# addonv2.net
KiCad netlist of a schematic drawn in EAGLE
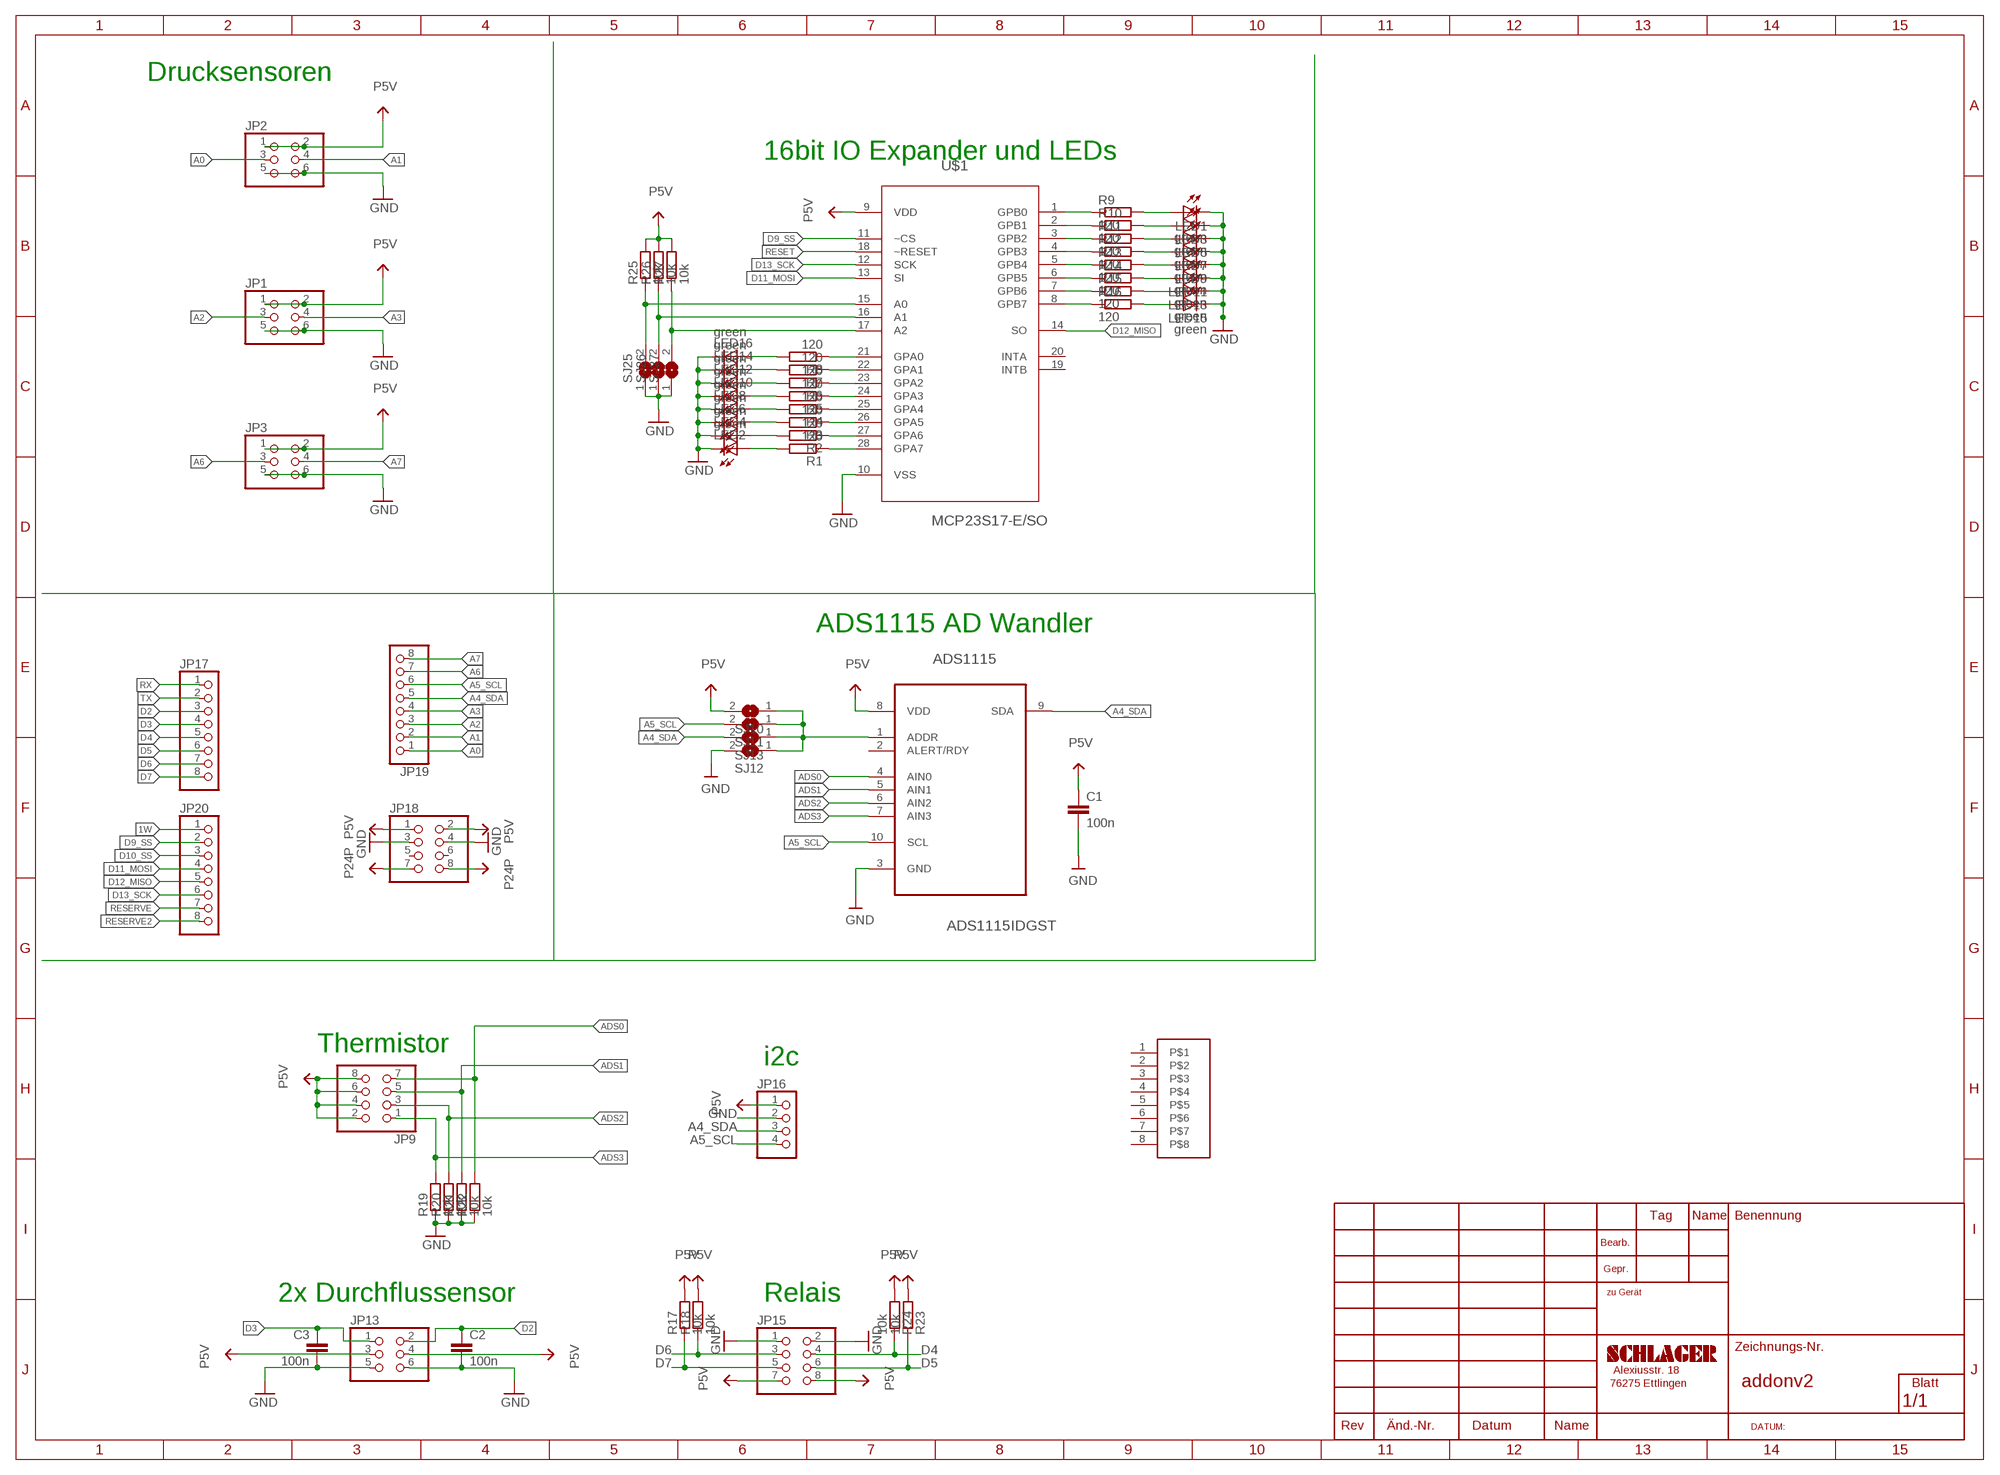
[diagram p0: schematic, sheet 1]

(export (version "E")
  (design (tool "Eeschema 10.0.6"))
  (components
    (comp (ref "ADS1115")
      (value "ADS1115IDGST")
      (footprint "eagle-import:SOP50P490X110-10N")
      (libsource (lib "eagle-import") (part "ADS1115IDGST"))
    )
    (comp (ref "C1")
      (value "100n")
      (footprint "eagle-import:C0805")
      (libsource (lib "eagle-import") (part "C-EUC0805"))
    )
    (comp (ref "C2")
      (value "100n")
      (footprint "eagle-import:C0805")
      (libsource (lib "eagle-import") (part "C-EUC0805"))
    )
    (comp (ref "C3")
      (value "100n")
      (footprint "eagle-import:C0805")
      (libsource (lib "eagle-import") (part "C-EUC0805"))
    )
    (comp (ref "JP1")
      (value "PINHD-2X3/90")
      (footprint "eagle-import:2X03_90")
      (libsource (lib "eagle-import") (part "PINHD-2X3/90"))
    )
    (comp (ref "JP2")
      (value "PINHD-2X3/90")
      (footprint "eagle-import:2X03_90")
      (libsource (lib "eagle-import") (part "PINHD-2X3/90"))
    )
    (comp (ref "JP3")
      (value "PINHD-2X3/90")
      (footprint "eagle-import:2X03_90")
      (libsource (lib "eagle-import") (part "PINHD-2X3/90"))
    )
    (comp (ref "JP9")
      (value "PINHD-2X4/90")
      (footprint "eagle-import:2X04_90")
      (libsource (lib "eagle-import") (part "PINHD-2X4/90"))
    )
    (comp (ref "JP13")
      (value "PINHD-2X3/90")
      (footprint "eagle-import:2X03_90")
      (libsource (lib "eagle-import") (part "PINHD-2X3/90"))
    )
    (comp (ref "JP15")
      (value "PINHD-2X4/90")
      (footprint "eagle-import:2X04_90")
      (libsource (lib "eagle-import") (part "PINHD-2X4/90"))
    )
    (comp (ref "JP16")
      (value "PINHD-1X4/90")
      (footprint "eagle-import:1X04_90")
      (libsource (lib "eagle-import") (part "PINHD-1X4/90"))
    )
    (comp (ref "JP17")
      (value "PINHD-1X8")
      (footprint "eagle-import:1X08")
      (libsource (lib "eagle-import") (part "PINHD-1X8"))
    )
    (comp (ref "JP18")
      (value "PINHD-2X4")
      (footprint "eagle-import:2X04")
      (libsource (lib "eagle-import") (part "PINHD-2X4"))
    )
    (comp (ref "JP19")
      (value "PINHD-1X8")
      (footprint "eagle-import:1X08")
      (libsource (lib "eagle-import") (part "PINHD-1X8"))
    )
    (comp (ref "JP20")
      (value "PINHD-1X8")
      (footprint "eagle-import:1X08")
      (libsource (lib "eagle-import") (part "PINHD-1X8"))
    )
    (comp (ref "LED1")
      (value "green")
      (footprint "eagle-import:CHIPLED_0805")
      (libsource (lib "eagle-import") (part "LEDCHIPLED_0805"))
    )
    (comp (ref "LED2")
      (value "green")
      (footprint "eagle-import:CHIPLED_0805")
      (libsource (lib "eagle-import") (part "LEDCHIPLED_0805"))
    )
    (comp (ref "LED3")
      (value "green")
      (footprint "eagle-import:CHIPLED_0805")
      (libsource (lib "eagle-import") (part "LEDCHIPLED_0805"))
    )
    (comp (ref "LED4")
      (value "green")
      (footprint "eagle-import:CHIPLED_0805")
      (libsource (lib "eagle-import") (part "LEDCHIPLED_0805"))
    )
    (comp (ref "LED5")
      (value "green")
      (footprint "eagle-import:CHIPLED_0805")
      (libsource (lib "eagle-import") (part "LEDCHIPLED_0805"))
    )
    (comp (ref "LED6")
      (value "green")
      (footprint "eagle-import:CHIPLED_0805")
      (libsource (lib "eagle-import") (part "LEDCHIPLED_0805"))
    )
    (comp (ref "LED7")
      (value "green")
      (footprint "eagle-import:CHIPLED_0805")
      (libsource (lib "eagle-import") (part "LEDCHIPLED_0805"))
    )
    (comp (ref "LED8")
      (value "green")
      (footprint "eagle-import:CHIPLED_0805")
      (libsource (lib "eagle-import") (part "LEDCHIPLED_0805"))
    )
    (comp (ref "LED9")
      (value "green")
      (footprint "eagle-import:CHIPLED_0805")
      (libsource (lib "eagle-import") (part "LEDCHIPLED_0805"))
    )
    (comp (ref "LED10")
      (value "green")
      (footprint "eagle-import:CHIPLED_0805")
      (libsource (lib "eagle-import") (part "LEDCHIPLED_0805"))
    )
    (comp (ref "LED11")
      (value "green")
      (footprint "eagle-import:CHIPLED_0805")
      (libsource (lib "eagle-import") (part "LEDCHIPLED_0805"))
    )
    (comp (ref "LED12")
      (value "green")
      (footprint "eagle-import:CHIPLED_0805")
      (libsource (lib "eagle-import") (part "LEDCHIPLED_0805"))
    )
    (comp (ref "LED13")
      (value "green")
      (footprint "eagle-import:CHIPLED_0805")
      (libsource (lib "eagle-import") (part "LEDCHIPLED_0805"))
    )
    (comp (ref "LED14")
      (value "green")
      (footprint "eagle-import:CHIPLED_0805")
      (libsource (lib "eagle-import") (part "LEDCHIPLED_0805"))
    )
    (comp (ref "LED15")
      (value "green")
      (footprint "eagle-import:CHIPLED_0805")
      (libsource (lib "eagle-import") (part "LEDCHIPLED_0805"))
    )
    (comp (ref "LED16")
      (value "green")
      (footprint "eagle-import:CHIPLED_0805")
      (libsource (lib "eagle-import") (part "LEDCHIPLED_0805"))
    )
    (comp (ref "R1")
      (value "120")
      (footprint "eagle-import:R0805")
      (libsource (lib "eagle-import") (part "R-EU_R0805"))
    )
    (comp (ref "R2")
      (value "120")
      (footprint "eagle-import:R0805")
      (libsource (lib "eagle-import") (part "R-EU_R0805"))
    )
    (comp (ref "R3")
      (value "120")
      (footprint "eagle-import:R0805")
      (libsource (lib "eagle-import") (part "R-EU_R0805"))
    )
    (comp (ref "R4")
      (value "120")
      (footprint "eagle-import:R0805")
      (libsource (lib "eagle-import") (part "R-EU_R0805"))
    )
    (comp (ref "R5")
      (value "120")
      (footprint "eagle-import:R0805")
      (libsource (lib "eagle-import") (part "R-EU_R0805"))
    )
    (comp (ref "R6")
      (value "120")
      (footprint "eagle-import:R0805")
      (libsource (lib "eagle-import") (part "R-EU_R0805"))
    )
    (comp (ref "R7")
      (value "120")
      (footprint "eagle-import:R0805")
      (libsource (lib "eagle-import") (part "R-EU_R0805"))
    )
    (comp (ref "R8")
      (value "120")
      (footprint "eagle-import:R0805")
      (libsource (lib "eagle-import") (part "R-EU_R0805"))
    )
    (comp (ref "R9")
      (value "120")
      (footprint "eagle-import:R0805")
      (libsource (lib "eagle-import") (part "R-EU_R0805"))
    )
    (comp (ref "R10")
      (value "120")
      (footprint "eagle-import:R0805")
      (libsource (lib "eagle-import") (part "R-EU_R0805"))
    )
    (comp (ref "R11")
      (value "120")
      (footprint "eagle-import:R0805")
      (libsource (lib "eagle-import") (part "R-EU_R0805"))
    )
    (comp (ref "R12")
      (value "120")
      (footprint "eagle-import:R0805")
      (libsource (lib "eagle-import") (part "R-EU_R0805"))
    )
    (comp (ref "R13")
      (value "120")
      (footprint "eagle-import:R0805")
      (libsource (lib "eagle-import") (part "R-EU_R0805"))
    )
    (comp (ref "R14")
      (value "120")
      (footprint "eagle-import:R0805")
      (libsource (lib "eagle-import") (part "R-EU_R0805"))
    )
    (comp (ref "R15")
      (value "120")
      (footprint "eagle-import:R0805")
      (libsource (lib "eagle-import") (part "R-EU_R0805"))
    )
    (comp (ref "R16")
      (value "120")
      (footprint "eagle-import:R0805")
      (libsource (lib "eagle-import") (part "R-EU_R0805"))
    )
    (comp (ref "R17")
      (value "10k")
      (footprint "eagle-import:R0805")
      (libsource (lib "eagle-import") (part "R-EU_R0805"))
    )
    (comp (ref "R18")
      (value "10k")
      (footprint "eagle-import:R0805")
      (libsource (lib "eagle-import") (part "R-EU_R0805"))
    )
    (comp (ref "R19")
      (value "10k")
      (footprint "eagle-import:R0805")
      (libsource (lib "eagle-import") (part "R-EU_R0805"))
    )
    (comp (ref "R20")
      (value "10k")
      (footprint "eagle-import:R0805")
      (libsource (lib "eagle-import") (part "R-EU_R0805"))
    )
    (comp (ref "R21")
      (value "10k")
      (footprint "eagle-import:R0805")
      (libsource (lib "eagle-import") (part "R-EU_R0805"))
    )
    (comp (ref "R22")
      (value "10k")
      (footprint "eagle-import:R0805")
      (libsource (lib "eagle-import") (part "R-EU_R0805"))
    )
    (comp (ref "R23")
      (value "10k")
      (footprint "eagle-import:R0805")
      (libsource (lib "eagle-import") (part "R-EU_R0805"))
    )
    (comp (ref "R24")
      (value "10k")
      (footprint "eagle-import:R0805")
      (libsource (lib "eagle-import") (part "R-EU_R0805"))
    )
    (comp (ref "R25")
      (value "10k")
      (footprint "eagle-import:R0805")
      (libsource (lib "eagle-import") (part "R-EU_R0805"))
    )
    (comp (ref "R26")
      (value "10k")
      (footprint "eagle-import:R0805")
      (libsource (lib "eagle-import") (part "R-EU_R0805"))
    )
    (comp (ref "R27")
      (value "10k")
      (footprint "eagle-import:R0805")
      (libsource (lib "eagle-import") (part "R-EU_R0805"))
    )
    (comp (ref "SJ10")
      (value "SJN")
      (footprint "eagle-import:SJ")
      (libsource (lib "eagle-import") (part "SJN"))
    )
    (comp (ref "SJ11")
      (value "SJN")
      (footprint "eagle-import:SJ")
      (libsource (lib "eagle-import") (part "SJN"))
    )
    (comp (ref "SJ12")
      (value "SJN")
      (footprint "eagle-import:SJ")
      (libsource (lib "eagle-import") (part "SJN"))
    )
    (comp (ref "SJ13")
      (value "SJN")
      (footprint "eagle-import:SJ")
      (libsource (lib "eagle-import") (part "SJN"))
    )
    (comp (ref "SJ25")
      (value "SJN")
      (footprint "eagle-import:SJ")
      (libsource (lib "eagle-import") (part "SJN"))
    )
    (comp (ref "SJ26")
      (value "SJN")
      (footprint "eagle-import:SJ")
      (libsource (lib "eagle-import") (part "SJN"))
    )
    (comp (ref "SJ27")
      (value "SJN")
      (footprint "eagle-import:SJ")
      (libsource (lib "eagle-import") (part "SJN"))
    )
    (comp (ref "U$1")
      (value "MCP23S17-E/SO")
      (footprint "eagle-import:SOIC127P030X265-28N")
      (libsource (lib "eagle-import") (part "MCP23S17-E/SO"))
    )
    (comp (ref "U$2")
      (value "1.44-128X128")
      (footprint "eagle-import:1.44-128X128")
      (libsource (lib "eagle-import") (part "1.44-128X128"))
    )
  )
  (nets
    (net (code "1") (name "1W") (class "Default")
      (node (ref "JP20") (pin "1") (pinfunction "1_1") (pintype "passive"))
    )
    (net (code "2") (name "A0") (class "Default")
      (node (ref "JP19") (pin "1") (pinfunction "1_1") (pintype "passive"))
      (node (ref "JP2") (pin "3") (pinfunction "3_3") (pintype "passive"))
    )
    (net (code "3") (name "A1") (class "Default")
      (node (ref "JP19") (pin "2") (pinfunction "2_2") (pintype "passive"))
      (node (ref "JP2") (pin "4") (pinfunction "4_4") (pintype "passive"))
    )
    (net (code "4") (name "A2") (class "Default")
      (node (ref "JP1") (pin "3") (pinfunction "3_3") (pintype "passive"))
      (node (ref "JP19") (pin "3") (pinfunction "3_3") (pintype "passive"))
    )
    (net (code "5") (name "A3") (class "Default")
      (node (ref "JP1") (pin "4") (pinfunction "4_4") (pintype "passive"))
      (node (ref "JP19") (pin "4") (pinfunction "4_4") (pintype "passive"))
    )
    (net (code "6") (name "A4_SDA") (class "Default")
      (node (ref "ADS1115") (pin "9") (pinfunction "SDA_9") (pintype "bidirectional"))
      (node (ref "JP16") (pin "3") (pinfunction "3_3") (pintype "passive"))
      (node (ref "JP19") (pin "5") (pinfunction "5_5") (pintype "passive"))
      (node (ref "SJ13") (pin "2") (pinfunction "2_2") (pintype "passive"))
    )
    (net (code "7") (name "A5_SCL") (class "Default")
      (node (ref "ADS1115") (pin "10") (pinfunction "SCL_10") (pintype "input"))
      (node (ref "JP16") (pin "4") (pinfunction "4_4") (pintype "passive"))
      (node (ref "JP19") (pin "6") (pinfunction "6_6") (pintype "passive"))
      (node (ref "SJ11") (pin "2") (pinfunction "2_2") (pintype "passive"))
    )
    (net (code "8") (name "A6") (class "Default")
      (node (ref "JP19") (pin "7") (pinfunction "7_7") (pintype "passive"))
      (node (ref "JP3") (pin "3") (pinfunction "3_3") (pintype "passive"))
    )
    (net (code "9") (name "A7") (class "Default")
      (node (ref "JP19") (pin "8") (pinfunction "8_8") (pintype "passive"))
      (node (ref "JP3") (pin "4") (pinfunction "4_4") (pintype "passive"))
    )
    (net (code "10") (name "ADS0") (class "Default")
      (node (ref "ADS1115") (pin "4") (pinfunction "AIN0_4") (pintype "input"))
      (node (ref "JP9") (pin "7") (pinfunction "7_7") (pintype "passive"))
      (node (ref "R22") (pin "2") (pinfunction "2_2") (pintype "passive"))
    )
    (net (code "11") (name "ADS1") (class "Default")
      (node (ref "ADS1115") (pin "5") (pinfunction "AIN1_5") (pintype "input"))
      (node (ref "JP9") (pin "5") (pinfunction "5_5") (pintype "passive"))
      (node (ref "R21") (pin "2") (pinfunction "2_2") (pintype "passive"))
    )
    (net (code "12") (name "ADS2") (class "Default")
      (node (ref "ADS1115") (pin "6") (pinfunction "AIN2_6") (pintype "input"))
      (node (ref "JP9") (pin "3") (pinfunction "3_3") (pintype "passive"))
      (node (ref "R20") (pin "2") (pinfunction "2_2") (pintype "passive"))
    )
    (net (code "13") (name "ADS3") (class "Default")
      (node (ref "ADS1115") (pin "7") (pinfunction "AIN3_7") (pintype "input"))
      (node (ref "JP9") (pin "1") (pinfunction "1_1") (pintype "passive"))
      (node (ref "R19") (pin "2") (pinfunction "2_2") (pintype "passive"))
    )
    (net (code "14") (name "D2") (class "Default")
      (node (ref "C2") (pin "1") (pinfunction "1_1") (pintype "passive"))
      (node (ref "JP13") (pin "2") (pinfunction "2_2") (pintype "passive"))
      (node (ref "JP17") (pin "3") (pinfunction "3_3") (pintype "passive"))
    )
    (net (code "15") (name "D3") (class "Default")
      (node (ref "C3") (pin "1") (pinfunction "1_1") (pintype "passive"))
      (node (ref "JP13") (pin "1") (pinfunction "1_1") (pintype "passive"))
      (node (ref "JP17") (pin "4") (pinfunction "4_4") (pintype "passive"))
    )
    (net (code "16") (name "D4") (class "Default")
      (node (ref "JP15") (pin "4") (pinfunction "4_4") (pintype "passive"))
      (node (ref "JP17") (pin "5") (pinfunction "5_5") (pintype "passive"))
      (node (ref "R24") (pin "1") (pinfunction "1_1") (pintype "passive"))
    )
    (net (code "17") (name "D5") (class "Default")
      (node (ref "JP15") (pin "6") (pinfunction "6_6") (pintype "passive"))
      (node (ref "JP17") (pin "6") (pinfunction "6_6") (pintype "passive"))
      (node (ref "R23") (pin "1") (pinfunction "1_1") (pintype "passive"))
    )
    (net (code "18") (name "D6") (class "Default")
      (node (ref "JP15") (pin "3") (pinfunction "3_3") (pintype "passive"))
      (node (ref "JP17") (pin "7") (pinfunction "7_7") (pintype "passive"))
      (node (ref "R18") (pin "1") (pinfunction "1_1") (pintype "passive"))
    )
    (net (code "19") (name "D7") (class "Default")
      (node (ref "JP15") (pin "5") (pinfunction "5_5") (pintype "passive"))
      (node (ref "JP17") (pin "8") (pinfunction "8_8") (pintype "passive"))
      (node (ref "R17") (pin "1") (pinfunction "1_1") (pintype "passive"))
    )
    (net (code "20") (name "D9_SS") (class "Default")
      (node (ref "JP20") (pin "2") (pinfunction "2_2") (pintype "passive"))
      (node (ref "U$1") (pin "11") (pinfunction "~{CS}_11") (pintype "input"))
    )
    (net (code "21") (name "D10_SS") (class "Default")
      (node (ref "JP20") (pin "3") (pinfunction "3_3") (pintype "passive"))
    )
    (net (code "22") (name "D11_MOSI") (class "Default")
      (node (ref "JP20") (pin "4") (pinfunction "4_4") (pintype "passive"))
      (node (ref "U$1") (pin "13") (pinfunction "SI_13") (pintype "input"))
    )
    (net (code "23") (name "D12_MISO") (class "Default")
      (node (ref "JP20") (pin "5") (pinfunction "5_5") (pintype "passive"))
      (node (ref "U$1") (pin "14") (pinfunction "SO_14") (pintype "output"))
    )
    (net (code "24") (name "D13_SCK") (class "Default")
      (node (ref "JP20") (pin "6") (pinfunction "6_6") (pintype "passive"))
      (node (ref "U$1") (pin "12") (pinfunction "SCK_12") (pintype "input"))
    )
    (net (code "25") (name "GND") (class "Default")
      (node (ref "ADS1115") (pin "3") (pinfunction "GND_3") (pintype "passive"))
      (node (ref "C1") (pin "2") (pinfunction "2_2") (pintype "passive"))
      (node (ref "C2") (pin "2") (pinfunction "2_2") (pintype "passive"))
      (node (ref "C3") (pin "2") (pinfunction "2_2") (pintype "passive"))
      (node (ref "JP1") (pin "5") (pinfunction "5_5") (pintype "passive"))
      (node (ref "JP1") (pin "6") (pinfunction "6_6") (pintype "passive"))
      (node (ref "JP13") (pin "5") (pinfunction "5_5") (pintype "passive"))
      (node (ref "JP13") (pin "6") (pinfunction "6_6") (pintype "passive"))
      (node (ref "JP15") (pin "1") (pinfunction "1_1") (pintype "passive"))
      (node (ref "JP15") (pin "2") (pinfunction "2_2") (pintype "passive"))
      (node (ref "JP16") (pin "2") (pinfunction "2_2") (pintype "passive"))
      (node (ref "JP18") (pin "3") (pinfunction "3_3") (pintype "passive"))
      (node (ref "JP18") (pin "4") (pinfunction "4_4") (pintype "passive"))
      (node (ref "JP2") (pin "5") (pinfunction "5_5") (pintype "passive"))
      (node (ref "JP2") (pin "6") (pinfunction "6_6") (pintype "passive"))
      (node (ref "JP3") (pin "5") (pinfunction "5_5") (pintype "passive"))
      (node (ref "JP3") (pin "6") (pinfunction "6_6") (pintype "passive"))
      (node (ref "LED1") (pin "C") (pinfunction "C_C") (pintype "passive"))
      (node (ref "LED10") (pin "C") (pinfunction "C_C") (pintype "passive"))
      (node (ref "LED11") (pin "C") (pinfunction "C_C") (pintype "passive"))
      (node (ref "LED12") (pin "C") (pinfunction "C_C") (pintype "passive"))
      (node (ref "LED13") (pin "C") (pinfunction "C_C") (pintype "passive"))
      (node (ref "LED14") (pin "C") (pinfunction "C_C") (pintype "passive"))
      (node (ref "LED15") (pin "C") (pinfunction "C_C") (pintype "passive"))
      (node (ref "LED16") (pin "C") (pinfunction "C_C") (pintype "passive"))
      (node (ref "LED2") (pin "C") (pinfunction "C_C") (pintype "passive"))
      (node (ref "LED3") (pin "C") (pinfunction "C_C") (pintype "passive"))
      (node (ref "LED4") (pin "C") (pinfunction "C_C") (pintype "passive"))
      (node (ref "LED5") (pin "C") (pinfunction "C_C") (pintype "passive"))
      (node (ref "LED6") (pin "C") (pinfunction "C_C") (pintype "passive"))
      (node (ref "LED7") (pin "C") (pinfunction "C_C") (pintype "passive"))
      (node (ref "LED8") (pin "C") (pinfunction "C_C") (pintype "passive"))
      (node (ref "LED9") (pin "C") (pinfunction "C_C") (pintype "passive"))
      (node (ref "R19") (pin "1") (pinfunction "1_1") (pintype "passive"))
      (node (ref "R20") (pin "1") (pinfunction "1_1") (pintype "passive"))
      (node (ref "R21") (pin "1") (pinfunction "1_1") (pintype "passive"))
      (node (ref "R22") (pin "1") (pinfunction "1_1") (pintype "passive"))
      (node (ref "SJ12") (pin "2") (pinfunction "2_2") (pintype "passive"))
      (node (ref "SJ25") (pin "1") (pinfunction "1_1") (pintype "passive"))
      (node (ref "SJ26") (pin "1") (pinfunction "1_1") (pintype "passive"))
      (node (ref "SJ27") (pin "1") (pinfunction "1_1") (pintype "passive"))
      (node (ref "U$1") (pin "10") (pinfunction "VSS_10") (pintype "power_in"))
    )
    (net (code "26") (name "Net-(ADS1115-ADDR)") (class "Default")
      (node (ref "ADS1115") (pin "1") (pinfunction "ADDR_1") (pintype "input"))
      (node (ref "SJ10") (pin "1") (pinfunction "1_1") (pintype "passive"))
      (node (ref "SJ11") (pin "1") (pinfunction "1_1") (pintype "passive"))
      (node (ref "SJ12") (pin "1") (pinfunction "1_1") (pintype "passive"))
      (node (ref "SJ13") (pin "1") (pinfunction "1_1") (pintype "passive"))
    )
    (net (code "27") (name "Net-(LED1-PadA)") (class "Default")
      (node (ref "LED1") (pin "A") (pinfunction "A_A") (pintype "passive"))
      (node (ref "R9") (pin "2") (pinfunction "2_2") (pintype "passive"))
    )
    (net (code "28") (name "Net-(LED2-PadA)") (class "Default")
      (node (ref "LED2") (pin "A") (pinfunction "A_A") (pintype "passive"))
      (node (ref "R1") (pin "2") (pinfunction "2_2") (pintype "passive"))
    )
    (net (code "29") (name "Net-(LED3-PadA)") (class "Default")
      (node (ref "LED3") (pin "A") (pinfunction "A_A") (pintype "passive"))
      (node (ref "R10") (pin "2") (pinfunction "2_2") (pintype "passive"))
    )
    (net (code "30") (name "Net-(LED4-PadA)") (class "Default")
      (node (ref "LED4") (pin "A") (pinfunction "A_A") (pintype "passive"))
      (node (ref "R2") (pin "2") (pinfunction "2_2") (pintype "passive"))
    )
    (net (code "31") (name "Net-(LED5-PadA)") (class "Default")
      (node (ref "LED5") (pin "A") (pinfunction "A_A") (pintype "passive"))
      (node (ref "R11") (pin "2") (pinfunction "2_2") (pintype "passive"))
    )
    (net (code "32") (name "Net-(LED6-PadA)") (class "Default")
      (node (ref "LED6") (pin "A") (pinfunction "A_A") (pintype "passive"))
      (node (ref "R3") (pin "2") (pinfunction "2_2") (pintype "passive"))
    )
    (net (code "33") (name "Net-(LED7-PadA)") (class "Default")
      (node (ref "LED7") (pin "A") (pinfunction "A_A") (pintype "passive"))
      (node (ref "R12") (pin "2") (pinfunction "2_2") (pintype "passive"))
    )
    (net (code "34") (name "Net-(LED8-PadA)") (class "Default")
      (node (ref "LED8") (pin "A") (pinfunction "A_A") (pintype "passive"))
      (node (ref "R4") (pin "2") (pinfunction "2_2") (pintype "passive"))
    )
    (net (code "35") (name "Net-(LED9-PadA)") (class "Default")
      (node (ref "LED9") (pin "A") (pinfunction "A_A") (pintype "passive"))
      (node (ref "R13") (pin "2") (pinfunction "2_2") (pintype "passive"))
    )
    (net (code "36") (name "Net-(LED10-PadA)") (class "Default")
      (node (ref "LED10") (pin "A") (pinfunction "A_A") (pintype "passive"))
      (node (ref "R5") (pin "2") (pinfunction "2_2") (pintype "passive"))
    )
    (net (code "37") (name "Net-(LED11-PadA)") (class "Default")
      (node (ref "LED11") (pin "A") (pinfunction "A_A") (pintype "passive"))
      (node (ref "R14") (pin "2") (pinfunction "2_2") (pintype "passive"))
    )
    (net (code "38") (name "Net-(LED12-PadA)") (class "Default")
      (node (ref "LED12") (pin "A") (pinfunction "A_A") (pintype "passive"))
      (node (ref "R6") (pin "2") (pinfunction "2_2") (pintype "passive"))
    )
    (net (code "39") (name "Net-(LED13-PadA)") (class "Default")
      (node (ref "LED13") (pin "A") (pinfunction "A_A") (pintype "passive"))
      (node (ref "R15") (pin "2") (pinfunction "2_2") (pintype "passive"))
    )
    (net (code "40") (name "Net-(LED14-PadA)") (class "Default")
      (node (ref "LED14") (pin "A") (pinfunction "A_A") (pintype "passive"))
      (node (ref "R7") (pin "2") (pinfunction "2_2") (pintype "passive"))
    )
    (net (code "41") (name "Net-(LED15-PadA)") (class "Default")
      (node (ref "LED15") (pin "A") (pinfunction "A_A") (pintype "passive"))
      (node (ref "R16") (pin "2") (pinfunction "2_2") (pintype "passive"))
    )
    (net (code "42") (name "Net-(LED16-PadA)") (class "Default")
      (node (ref "LED16") (pin "A") (pinfunction "A_A") (pintype "passive"))
      (node (ref "R8") (pin "2") (pinfunction "2_2") (pintype "passive"))
    )
    (net (code "43") (name "Net-(U$1-A0)") (class "Default")
      (node (ref "R25") (pin "1") (pinfunction "1_1") (pintype "passive"))
      (node (ref "SJ25") (pin "2") (pinfunction "2_2") (pintype "passive"))
      (node (ref "U$1") (pin "15") (pinfunction "A0_15") (pintype "input"))
    )
    (net (code "44") (name "Net-(U$1-A1)") (class "Default")
      (node (ref "R26") (pin "1") (pinfunction "1_1") (pintype "passive"))
      (node (ref "SJ26") (pin "2") (pinfunction "2_2") (pintype "passive"))
      (node (ref "U$1") (pin "16") (pinfunction "A1_16") (pintype "input"))
    )
    (net (code "45") (name "Net-(U$1-A2)") (class "Default")
      (node (ref "R27") (pin "1") (pinfunction "1_1") (pintype "passive"))
      (node (ref "SJ27") (pin "2") (pinfunction "2_2") (pintype "passive"))
      (node (ref "U$1") (pin "17") (pinfunction "A2_17") (pintype "input"))
    )
    (net (code "46") (name "Net-(U$1-GPA0)") (class "Default")
      (node (ref "R8") (pin "1") (pinfunction "1_1") (pintype "passive"))
      (node (ref "U$1") (pin "21") (pinfunction "GPA0_21") (pintype "bidirectional"))
    )
    (net (code "47") (name "Net-(U$1-GPA1)") (class "Default")
      (node (ref "R7") (pin "1") (pinfunction "1_1") (pintype "passive"))
      (node (ref "U$1") (pin "22") (pinfunction "GPA1_22") (pintype "bidirectional"))
    )
    (net (code "48") (name "Net-(U$1-GPA2)") (class "Default")
      (node (ref "R6") (pin "1") (pinfunction "1_1") (pintype "passive"))
      (node (ref "U$1") (pin "23") (pinfunction "GPA2_23") (pintype "bidirectional"))
    )
    (net (code "49") (name "Net-(U$1-GPA3)") (class "Default")
      (node (ref "R5") (pin "1") (pinfunction "1_1") (pintype "passive"))
      (node (ref "U$1") (pin "24") (pinfunction "GPA3_24") (pintype "bidirectional"))
    )
    (net (code "50") (name "Net-(U$1-GPA4)") (class "Default")
      (node (ref "R4") (pin "1") (pinfunction "1_1") (pintype "passive"))
      (node (ref "U$1") (pin "25") (pinfunction "GPA4_25") (pintype "bidirectional"))
    )
    (net (code "51") (name "Net-(U$1-GPA5)") (class "Default")
      (node (ref "R3") (pin "1") (pinfunction "1_1") (pintype "passive"))
      (node (ref "U$1") (pin "26") (pinfunction "GPA5_26") (pintype "bidirectional"))
    )
    (net (code "52") (name "Net-(U$1-GPA6)") (class "Default")
      (node (ref "R2") (pin "1") (pinfunction "1_1") (pintype "passive"))
      (node (ref "U$1") (pin "27") (pinfunction "GPA6_27") (pintype "bidirectional"))
    )
    (net (code "53") (name "Net-(U$1-GPA7)") (class "Default")
      (node (ref "R1") (pin "1") (pinfunction "1_1") (pintype "passive"))
      (node (ref "U$1") (pin "28") (pinfunction "GPA7_28") (pintype "bidirectional"))
    )
    (net (code "54") (name "Net-(U$1-GPB0)") (class "Default")
      (node (ref "R9") (pin "1") (pinfunction "1_1") (pintype "passive"))
      (node (ref "U$1") (pin "1") (pinfunction "GPB0_1") (pintype "bidirectional"))
    )
    (net (code "55") (name "Net-(U$1-GPB1)") (class "Default")
      (node (ref "R10") (pin "1") (pinfunction "1_1") (pintype "passive"))
      (node (ref "U$1") (pin "2") (pinfunction "GPB1_2") (pintype "bidirectional"))
    )
    (net (code "56") (name "Net-(U$1-GPB2)") (class "Default")
      (node (ref "R11") (pin "1") (pinfunction "1_1") (pintype "passive"))
      (node (ref "U$1") (pin "3") (pinfunction "GPB2_3") (pintype "bidirectional"))
    )
    (net (code "57") (name "Net-(U$1-GPB3)") (class "Default")
      (node (ref "R12") (pin "1") (pinfunction "1_1") (pintype "passive"))
      (node (ref "U$1") (pin "4") (pinfunction "GPB3_4") (pintype "bidirectional"))
    )
    (net (code "58") (name "Net-(U$1-GPB4)") (class "Default")
      (node (ref "R13") (pin "1") (pinfunction "1_1") (pintype "passive"))
      (node (ref "U$1") (pin "5") (pinfunction "GPB4_5") (pintype "bidirectional"))
    )
    (net (code "59") (name "Net-(U$1-GPB5)") (class "Default")
      (node (ref "R14") (pin "1") (pinfunction "1_1") (pintype "passive"))
      (node (ref "U$1") (pin "6") (pinfunction "GPB5_6") (pintype "bidirectional"))
    )
    (net (code "60") (name "Net-(U$1-GPB6)") (class "Default")
      (node (ref "R15") (pin "1") (pinfunction "1_1") (pintype "passive"))
      (node (ref "U$1") (pin "7") (pinfunction "GPB6_7") (pintype "bidirectional"))
    )
    (net (code "61") (name "Net-(U$1-GPB7)") (class "Default")
      (node (ref "R16") (pin "1") (pinfunction "1_1") (pintype "passive"))
      (node (ref "U$1") (pin "8") (pinfunction "GPB7_8") (pintype "bidirectional"))
    )
    (net (code "62") (name "P5V") (class "Default")
      (node (ref "ADS1115") (pin "8") (pinfunction "VDD_8") (pintype "power_in"))
      (node (ref "C1") (pin "1") (pinfunction "1_1") (pintype "passive"))
      (node (ref "JP1") (pin "1") (pinfunction "1_1") (pintype "passive"))
      (node (ref "JP1") (pin "2") (pinfunction "2_2") (pintype "passive"))
      (node (ref "JP13") (pin "3") (pinfunction "3_3") (pintype "passive"))
      (node (ref "JP13") (pin "4") (pinfunction "4_4") (pintype "passive"))
      (node (ref "JP15") (pin "7") (pinfunction "7_7") (pintype "passive"))
      (node (ref "JP15") (pin "8") (pinfunction "8_8") (pintype "passive"))
      (node (ref "JP16") (pin "1") (pinfunction "1_1") (pintype "passive"))
      (node (ref "JP18") (pin "1") (pinfunction "1_1") (pintype "passive"))
      (node (ref "JP18") (pin "2") (pinfunction "2_2") (pintype "passive"))
      (node (ref "JP2") (pin "1") (pinfunction "1_1") (pintype "passive"))
      (node (ref "JP2") (pin "2") (pinfunction "2_2") (pintype "passive"))
      (node (ref "JP3") (pin "1") (pinfunction "1_1") (pintype "passive"))
      (node (ref "JP3") (pin "2") (pinfunction "2_2") (pintype "passive"))
      (node (ref "JP9") (pin "2") (pinfunction "2_2") (pintype "passive"))
      (node (ref "JP9") (pin "4") (pinfunction "4_4") (pintype "passive"))
      (node (ref "JP9") (pin "6") (pinfunction "6_6") (pintype "passive"))
      (node (ref "JP9") (pin "8") (pinfunction "8_8") (pintype "passive"))
      (node (ref "R17") (pin "2") (pinfunction "2_2") (pintype "passive"))
      (node (ref "R18") (pin "2") (pinfunction "2_2") (pintype "passive"))
      (node (ref "R23") (pin "2") (pinfunction "2_2") (pintype "passive"))
      (node (ref "R24") (pin "2") (pinfunction "2_2") (pintype "passive"))
      (node (ref "R25") (pin "2") (pinfunction "2_2") (pintype "passive"))
      (node (ref "R26") (pin "2") (pinfunction "2_2") (pintype "passive"))
      (node (ref "R27") (pin "2") (pinfunction "2_2") (pintype "passive"))
      (node (ref "SJ10") (pin "2") (pinfunction "2_2") (pintype "passive"))
      (node (ref "U$1") (pin "9") (pinfunction "VDD_9") (pintype "power_in"))
    )
    (net (code "63") (name "P24P") (class "Default")
      (node (ref "JP18") (pin "7") (pinfunction "7_7") (pintype "passive"))
      (node (ref "JP18") (pin "8") (pinfunction "8_8") (pintype "passive"))
    )
    (net (code "64") (name "RESERVE") (class "Default")
      (node (ref "JP20") (pin "7") (pinfunction "7_7") (pintype "passive"))
    )
    (net (code "65") (name "RESERVE2") (class "Default")
      (node (ref "JP20") (pin "8") (pinfunction "8_8") (pintype "passive"))
    )
    (net (code "66") (name "RESET") (class "Default")
      (node (ref "U$1") (pin "18") (pinfunction "~{RESET}_18") (pintype "input"))
    )
    (net (code "67") (name "RX") (class "Default")
      (node (ref "JP17") (pin "1") (pinfunction "1_1") (pintype "passive"))
    )
    (net (code "68") (name "TX") (class "Default")
      (node (ref "JP17") (pin "2") (pinfunction "2_2") (pintype "passive"))
    )
    (net (code "69") (name "unconnected-(ADS1115-ALERT{slash}RDY-Pad2)") (class "Default")
      (node (ref "ADS1115") (pin "2") (pinfunction "ALERT/RDY_2") (pintype "input"))
    )
    (net (code "70") (name "unconnected-(JP18-Pad5)") (class "Default")
      (node (ref "JP18") (pin "5") (pinfunction "5_5") (pintype "passive"))
    )
    (net (code "71") (name "unconnected-(JP18-Pad6)") (class "Default")
      (node (ref "JP18") (pin "6") (pinfunction "6_6") (pintype "passive"))
    )
    (net (code "72") (name "unconnected-(U$1-INTA-Pad20)") (class "Default")
      (node (ref "U$1") (pin "20") (pinfunction "INTA_20") (pintype "output"))
    )
    (net (code "73") (name "unconnected-(U$1-INTB-Pad19)") (class "Default")
      (node (ref "U$1") (pin "19") (pinfunction "INTB_19") (pintype "output"))
    )
    (net (code "74") (name "unconnected-(U$2-P$1-Pad1)") (class "Default")
      (node (ref "U$2") (pin "1") (pinfunction "P$1_1") (pintype "bidirectional"))
    )
    (net (code "75") (name "unconnected-(U$2-P$2-Pad2)") (class "Default")
      (node (ref "U$2") (pin "2") (pinfunction "P$2_2") (pintype "bidirectional"))
    )
    (net (code "76") (name "unconnected-(U$2-P$3-Pad3)") (class "Default")
      (node (ref "U$2") (pin "3") (pinfunction "P$3_3") (pintype "bidirectional"))
    )
    (net (code "77") (name "unconnected-(U$2-P$4-Pad4)") (class "Default")
      (node (ref "U$2") (pin "4") (pinfunction "P$4_4") (pintype "bidirectional"))
    )
    (net (code "78") (name "unconnected-(U$2-P$5-Pad5)") (class "Default")
      (node (ref "U$2") (pin "5") (pinfunction "P$5_5") (pintype "bidirectional"))
    )
    (net (code "79") (name "unconnected-(U$2-P$6-Pad6)") (class "Default")
      (node (ref "U$2") (pin "6") (pinfunction "P$6_6") (pintype "bidirectional"))
    )
    (net (code "80") (name "unconnected-(U$2-P$7-Pad7)") (class "Default")
      (node (ref "U$2") (pin "7") (pinfunction "P$7_7") (pintype "bidirectional"))
    )
    (net (code "81") (name "unconnected-(U$2-P$8-Pad8)") (class "Default")
      (node (ref "U$2") (pin "8") (pinfunction "P$8_8") (pintype "bidirectional"))
    )
  )
)
